# interceptor.net
KiCad netlist of a schematic drawn in EAGLE
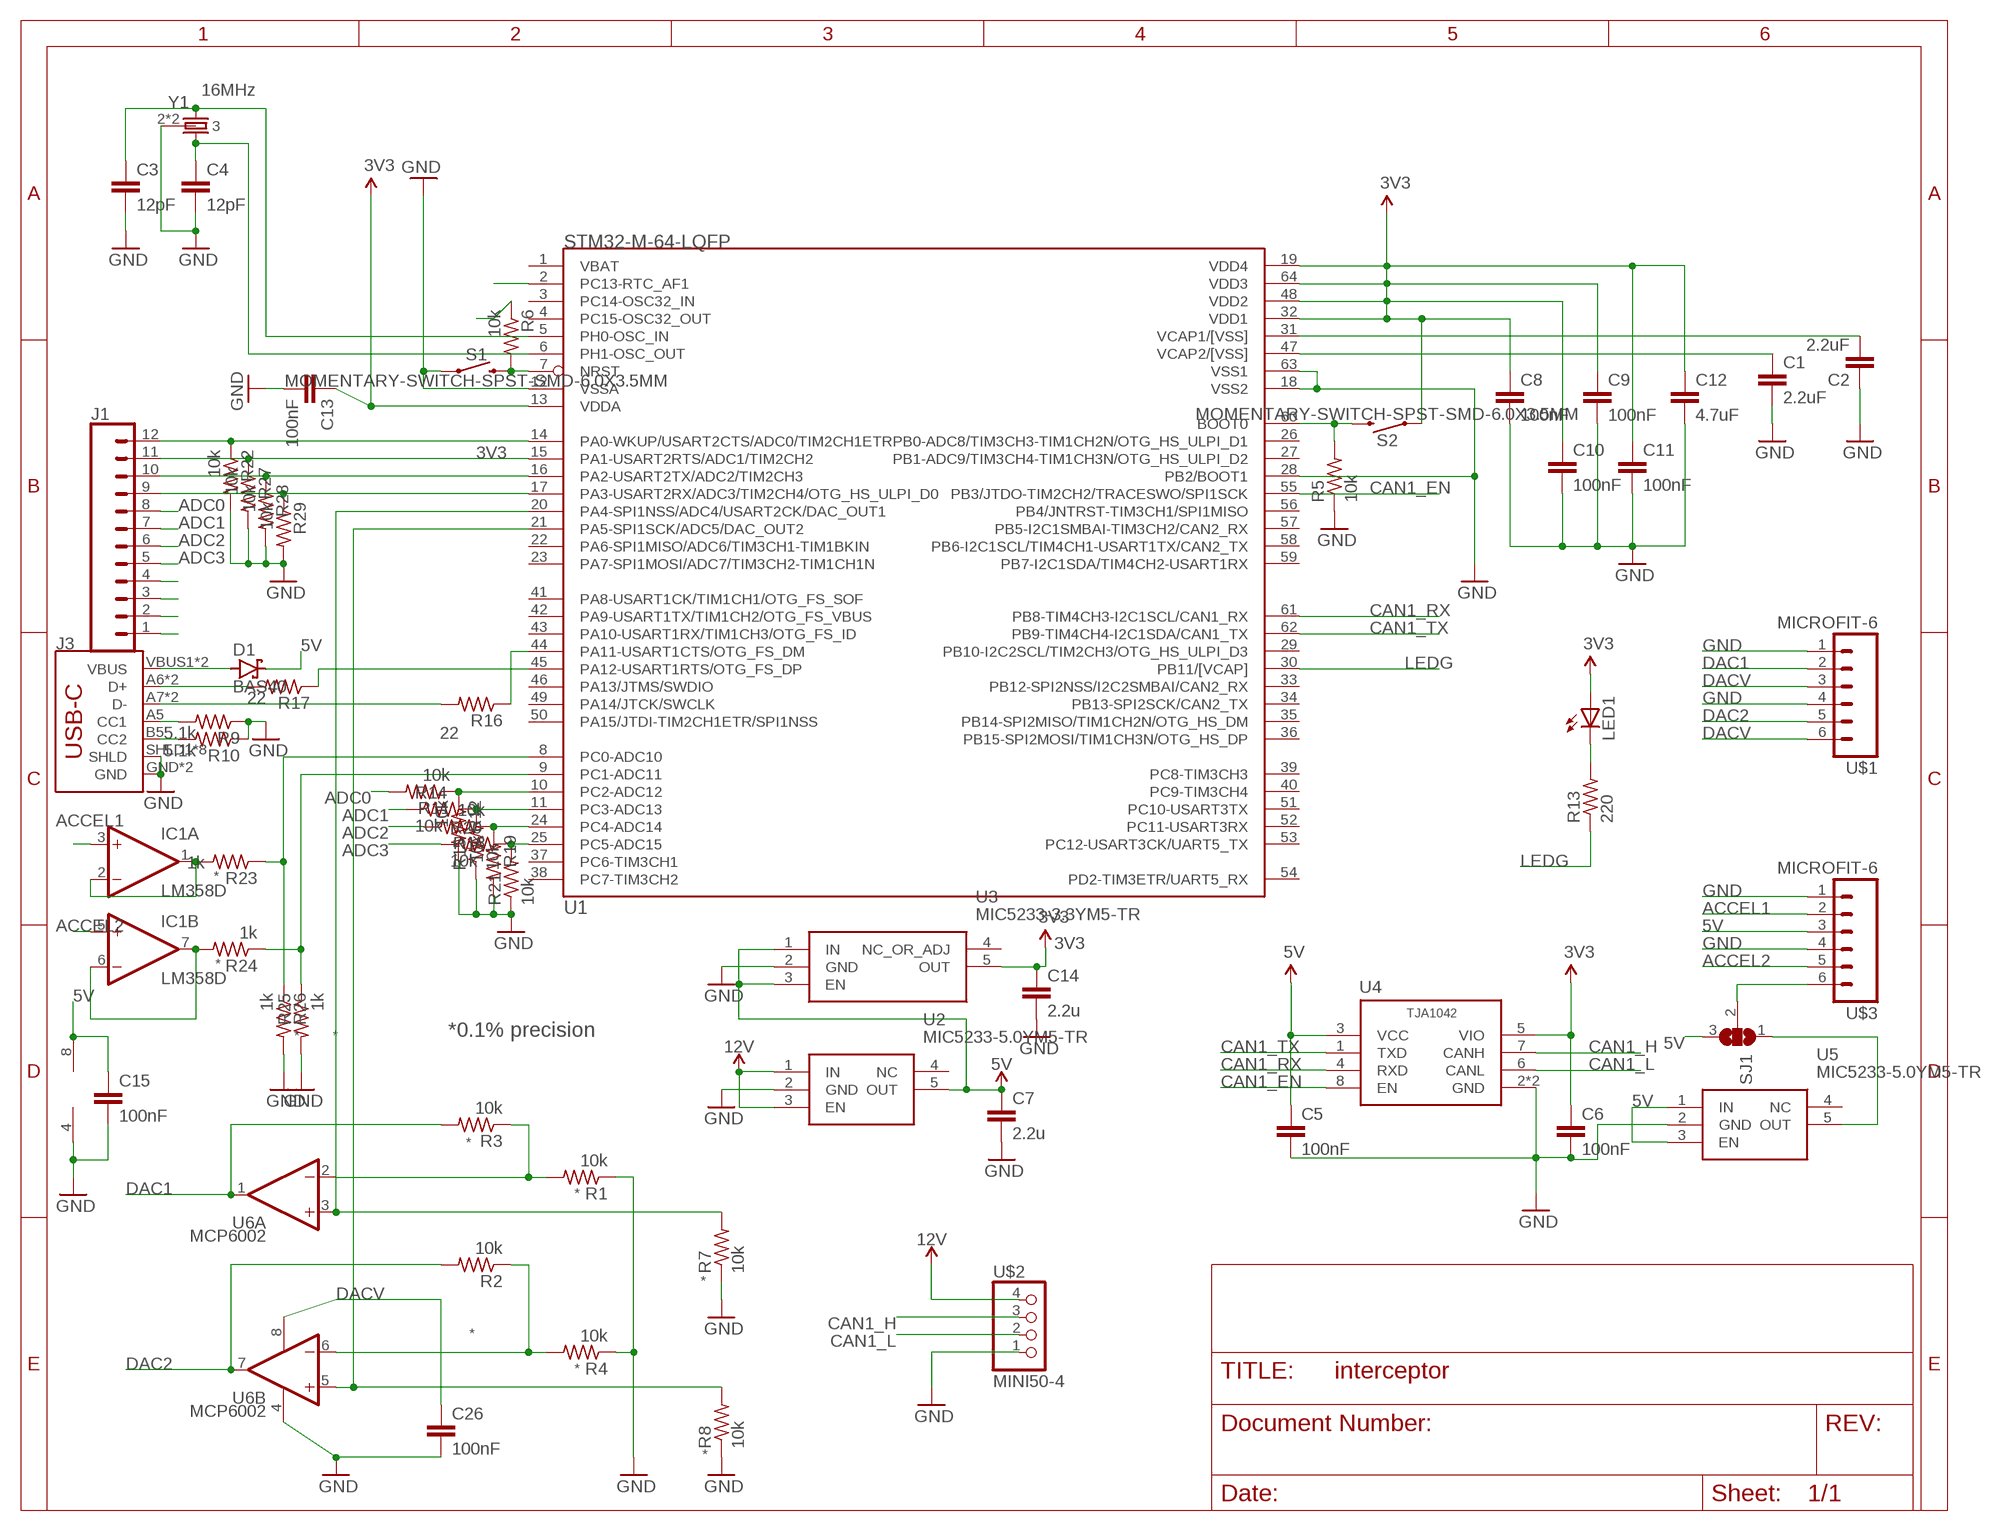
[diagram p0: schematic, sheet 1]

(export (version "E")
  (design (tool "Eeschema 10.0.6"))
  (components
    (comp (ref "C1")
      (value "2.2uF")
      (footprint "eagle-import:0603-C")
      (libsource (lib "eagle-import") (part "C0603"))
    )
    (comp (ref "C2")
      (value "2.2uF")
      (footprint "eagle-import:0603-C")
      (libsource (lib "eagle-import") (part "C0603"))
    )
    (comp (ref "C3")
      (value "12pF")
      (footprint "eagle-import:0603-C")
      (libsource (lib "eagle-import") (part "C0603"))
    )
    (comp (ref "C4")
      (value "12pF")
      (footprint "eagle-import:0603-C")
      (libsource (lib "eagle-import") (part "C0603"))
    )
    (comp (ref "C5")
      (value "100nF")
      (footprint "eagle-import:0603-C")
      (libsource (lib "eagle-import") (part "C0603"))
    )
    (comp (ref "C6")
      (value "100nF")
      (footprint "eagle-import:0603-C")
      (libsource (lib "eagle-import") (part "C0603"))
    )
    (comp (ref "C7")
      (value "2.2u")
      (footprint "eagle-import:C0603")
      (libsource (lib "eagle-import") (part "C-EUC0603"))
    )
    (comp (ref "C8")
      (value "100nF")
      (footprint "eagle-import:0603-C")
      (libsource (lib "eagle-import") (part "C0603"))
    )
    (comp (ref "C9")
      (value "100nF")
      (footprint "eagle-import:0603-C")
      (libsource (lib "eagle-import") (part "C0603"))
    )
    (comp (ref "C10")
      (value "100nF")
      (footprint "eagle-import:0603-C")
      (libsource (lib "eagle-import") (part "C0603"))
    )
    (comp (ref "C11")
      (value "100nF")
      (footprint "eagle-import:0603-C")
      (libsource (lib "eagle-import") (part "C0603"))
    )
    (comp (ref "C12")
      (value "4.7uF")
      (footprint "eagle-import:0603-C")
      (libsource (lib "eagle-import") (part "C0603"))
    )
    (comp (ref "C13")
      (value "100nF")
      (footprint "eagle-import:0603-C")
      (libsource (lib "eagle-import") (part "C0603"))
    )
    (comp (ref "C14")
      (value "2.2u")
      (footprint "eagle-import:C0603")
      (libsource (lib "eagle-import") (part "C-EUC0603"))
    )
    (comp (ref "C15")
      (value "100nF")
      (footprint "eagle-import:0603-C")
      (libsource (lib "eagle-import") (part "C0603"))
    )
    (comp (ref "C26")
      (value "100nF")
      (footprint "eagle-import:0603-C")
      (libsource (lib "eagle-import") (part "C0603"))
    )
    (comp (ref "D1")
      (value "BAS40")
      (footprint "eagle-import:SOT23")
      (libsource (lib "eagle-import") (part "BAS40"))
    )
    (comp (ref "IC1")
      (value "LM358D")
      (footprint "eagle-import:SO08")
      (libsource (lib "eagle-import") (part "LM358D"))
    )
    (comp (ref "J1")
      (value "CONN_12")
      (footprint "eagle-import:1X12")
      (libsource (lib "eagle-import") (part "CONN_12"))
    )
    (comp (ref "J3")
      (value "USB-C-BREAKOUT_SPARKFUN-CONNECTORS_USB_C16PIN")
      (footprint "eagle-import:USB-C-BREAKOUT_SPARKFUN-CONNECTORS_USB-C-16P")
      (libsource (lib "eagle-import") (part "USB-C-BREAKOUT_SPARKFUN-CONNECTORS_USB_C16PIN"))
    )
    (comp (ref "LED1")
      (value "LEDCHIPLED_0805")
      (footprint "eagle-import:CHIPLED_0805")
      (libsource (lib "eagle-import") (part "LEDCHIPLED_0805"))
    )
    (comp (ref "R1")
      (value "10k")
      (footprint "eagle-import:0402-R")
      (libsource (lib "eagle-import") (part "R0402"))
    )
    (comp (ref "R2")
      (value "10k")
      (footprint "eagle-import:0402-R")
      (libsource (lib "eagle-import") (part "R0402"))
    )
    (comp (ref "R3")
      (value "10k")
      (footprint "eagle-import:0402-R")
      (libsource (lib "eagle-import") (part "R0402"))
    )
    (comp (ref "R4")
      (value "10k")
      (footprint "eagle-import:0402-R")
      (libsource (lib "eagle-import") (part "R0402"))
    )
    (comp (ref "R5")
      (value "10k")
      (footprint "eagle-import:0402-R")
      (libsource (lib "eagle-import") (part "R0402"))
    )
    (comp (ref "R6")
      (value "10k")
      (footprint "eagle-import:0402-R")
      (libsource (lib "eagle-import") (part "R0402"))
    )
    (comp (ref "R7")
      (value "10k")
      (footprint "eagle-import:0402-R")
      (libsource (lib "eagle-import") (part "R0402"))
    )
    (comp (ref "R8")
      (value "10k")
      (footprint "eagle-import:0402-R")
      (libsource (lib "eagle-import") (part "R0402"))
    )
    (comp (ref "R9")
      (value "5.1k")
      (footprint "eagle-import:0402-R")
      (libsource (lib "eagle-import") (part "R0402"))
    )
    (comp (ref "R10")
      (value "5.1k")
      (footprint "eagle-import:0402-R")
      (libsource (lib "eagle-import") (part "R0402"))
    )
    (comp (ref "R11")
      (value "10k")
      (footprint "eagle-import:0402-R")
      (libsource (lib "eagle-import") (part "R0402"))
    )
    (comp (ref "R12")
      (value "10k")
      (footprint "eagle-import:0402-R")
      (libsource (lib "eagle-import") (part "R0402"))
    )
    (comp (ref "R13")
      (value "220")
      (footprint "eagle-import:0402-R")
      (libsource (lib "eagle-import") (part "R0402"))
    )
    (comp (ref "R14")
      (value "10k")
      (footprint "eagle-import:0402-R")
      (libsource (lib "eagle-import") (part "R0402"))
    )
    (comp (ref "R15")
      (value "10k")
      (footprint "eagle-import:0402-R")
      (libsource (lib "eagle-import") (part "R0402"))
    )
    (comp (ref "R16")
      (value "22")
      (footprint "eagle-import:0402-R")
      (libsource (lib "eagle-import") (part "R0402"))
    )
    (comp (ref "R17")
      (value "22")
      (footprint "eagle-import:0402-R")
      (libsource (lib "eagle-import") (part "R0402"))
    )
    (comp (ref "R18")
      (value "10k")
      (footprint "eagle-import:0402-R")
      (libsource (lib "eagle-import") (part "R0402"))
    )
    (comp (ref "R19")
      (value "10k")
      (footprint "eagle-import:0402-R")
      (libsource (lib "eagle-import") (part "R0402"))
    )
    (comp (ref "R20")
      (value "10k")
      (footprint "eagle-import:0402-R")
      (libsource (lib "eagle-import") (part "R0402"))
    )
    (comp (ref "R21")
      (value "10k")
      (footprint "eagle-import:0402-R")
      (libsource (lib "eagle-import") (part "R0402"))
    )
    (comp (ref "R22")
      (value "10k")
      (footprint "eagle-import:0402-R")
      (libsource (lib "eagle-import") (part "R0402"))
    )
    (comp (ref "R23")
      (value "1k")
      (footprint "eagle-import:0402-R")
      (libsource (lib "eagle-import") (part "R0402"))
    )
    (comp (ref "R24")
      (value "1k")
      (footprint "eagle-import:0402-R")
      (libsource (lib "eagle-import") (part "R0402"))
    )
    (comp (ref "R25")
      (value "1k")
      (footprint "eagle-import:0402-R")
      (libsource (lib "eagle-import") (part "R0402"))
    )
    (comp (ref "R26")
      (value "1k")
      (footprint "eagle-import:0402-R")
      (libsource (lib "eagle-import") (part "R0402"))
    )
    (comp (ref "R27")
      (value "10k")
      (footprint "eagle-import:0402-R")
      (libsource (lib "eagle-import") (part "R0402"))
    )
    (comp (ref "R28")
      (value "10k")
      (footprint "eagle-import:0402-R")
      (libsource (lib "eagle-import") (part "R0402"))
    )
    (comp (ref "R29")
      (value "10k")
      (footprint "eagle-import:0402-R")
      (libsource (lib "eagle-import") (part "R0402"))
    )
    (comp (ref "S1")
      (value "MOMENTARY-SWITCH-SPST-SMD-6.0X3.5MM")
      (footprint "eagle-import:TACTILE_SWITCH_SMD_6.0X3.5MM")
      (libsource (lib "eagle-import") (part "MOMENTARY-SWITCH-SPST-SMD-6.0X3.5MM"))
    )
    (comp (ref "S2")
      (value "MOMENTARY-SWITCH-SPST-SMD-6.0X3.5MM")
      (footprint "eagle-import:TACTILE_SWITCH_SMD_6.0X3.5MM")
      (libsource (lib "eagle-import") (part "MOMENTARY-SWITCH-SPST-SMD-6.0X3.5MM"))
    )
    (comp (ref "SJ1")
      (value "SJ2W")
      (footprint "eagle-import:SJ_2")
      (libsource (lib "eagle-import") (part "SJ2W"))
    )
    (comp (ref "U$1")
      (value "MICROFIT-6")
      (footprint "eagle-import:MICROFIT-6")
      (libsource (lib "eagle-import") (part "MICROFIT-6"))
    )
    (comp (ref "U$2")
      (value "MINI50-4")
      (footprint "eagle-import:MINI50")
      (libsource (lib "eagle-import") (part "MINI50-4"))
    )
    (comp (ref "U$3")
      (value "MICROFIT-6")
      (footprint "eagle-import:MICROFIT-6")
      (libsource (lib "eagle-import") (part "MICROFIT-6"))
    )
    (comp (ref "U1")
      (value "STM32-M-64-LQFP")
      (footprint "eagle-import:LQFP64")
      (libsource (lib "eagle-import") (part "STM32-M-64-LQFP"))
    )
    (comp (ref "U2")
      (value "MIC5233-5.0YM5-TR")
      (footprint "eagle-import:SOT95P280X145-5N")
      (fields (field (name "MOUSER_PART_NUMBER") "998-MIC5233-5.0YM5TR"))
      (libsource (lib "eagle-import") (part "MIC5233-5.0YM5-TR"))
    )
    (comp (ref "U3")
      (value "MIC5233-3.3YM5-TR")
      (footprint "eagle-import:SOT95P280X145-5N")
      (fields (field (name "MOUSER_PART_NUMBER") "998-MIC5233-3.3YM5TR"))
      (libsource (lib "eagle-import") (part "MIC5233-3.3YM5-TR"))
    )
    (comp (ref "U4")
      (value "TJA1042HVSON")
      (footprint "eagle-import:HVSON8")
      (libsource (lib "eagle-import") (part "TJA1042HVSON"))
    )
    (comp (ref "U5")
      (value "MIC5233-5.0YM5-TR")
      (footprint "eagle-import:SOT95P280X145-5N")
      (fields (field (name "MOUSER_PART_NUMBER") "998-MIC5233-5.0YM5TR"))
      (libsource (lib "eagle-import") (part "MIC5233-5.0YM5-TR"))
    )
    (comp (ref "U6")
      (value "MCP6002")
      (footprint "eagle-import:SO08")
      (libsource (lib "eagle-import") (part "LM358D"))
    )
    (comp (ref "Y1")
      (value "16MHz")
      (footprint "eagle-import:XTAL-3.2X2.5")
      (libsource (lib "eagle-import") (part "CRYSTAL-3.2X2.54-PIN"))
    )
  )
  (nets
    (net (code "1") (name "/ACCEL1") (class "Default")
      (node (ref "IC1") (pin "3") (pinfunction "+IN_3") (pintype "input"))
      (node (ref "U$3") (pin "2") (pinfunction "2_2") (pintype "passive"))
    )
    (net (code "2") (name "/ACCEL2") (class "Default")
      (node (ref "IC1") (pin "5") (pinfunction "+IN_5") (pintype "input"))
      (node (ref "U$3") (pin "5") (pinfunction "5_5") (pintype "passive"))
    )
    (net (code "3") (name "/ADC0") (class "Default")
      (node (ref "J1") (pin "8") (pinfunction "8_8") (pintype "passive"))
      (node (ref "R11") (pin "2") (pinfunction "2_2") (pintype "passive"))
    )
    (net (code "4") (name "/ADC1") (class "Default")
      (node (ref "J1") (pin "7") (pinfunction "7_7") (pintype "passive"))
      (node (ref "R14") (pin "1") (pinfunction "1_1") (pintype "passive"))
    )
    (net (code "5") (name "/ADC2") (class "Default")
      (node (ref "J1") (pin "6") (pinfunction "6_6") (pintype "passive"))
      (node (ref "R18") (pin "2") (pinfunction "2_2") (pintype "passive"))
    )
    (net (code "6") (name "/ADC3") (class "Default")
      (node (ref "J1") (pin "5") (pinfunction "5_5") (pintype "passive"))
      (node (ref "R20") (pin "1") (pinfunction "1_1") (pintype "passive"))
    )
    (net (code "7") (name "/CAN1_EN") (class "Default")
      (node (ref "U1") (pin "55") (pinfunction "PB3/JTDO-TIM2CH2/TRACESWO/SPI1SCK_55") (pintype "bidirectional"))
      (node (ref "U4") (pin "8") (pinfunction "EN_8") (pintype "bidirectional"))
    )
    (net (code "8") (name "/CAN1_H") (class "Default")
      (node (ref "U$2") (pin "3") (pinfunction "2_3") (pintype "passive"))
      (node (ref "U4") (pin "7") (pinfunction "CANH_7") (pintype "bidirectional"))
    )
    (net (code "9") (name "/CAN1_L") (class "Default")
      (node (ref "U$2") (pin "2") (pinfunction "3_2") (pintype "passive"))
      (node (ref "U4") (pin "6") (pinfunction "CANL_6") (pintype "bidirectional"))
    )
    (net (code "10") (name "/CAN1_RX") (class "Default")
      (node (ref "U1") (pin "61") (pinfunction "PB8-TIM4CH3-I2C1SCL/CAN1_RX_61") (pintype "bidirectional"))
      (node (ref "U4") (pin "4") (pinfunction "RXD_4") (pintype "bidirectional"))
    )
    (net (code "11") (name "/CAN1_TX") (class "Default")
      (node (ref "U1") (pin "62") (pinfunction "PB9-TIM4CH4-I2C1SDA/CAN1_TX_62") (pintype "bidirectional"))
      (node (ref "U4") (pin "1") (pinfunction "TXD_1") (pintype "bidirectional"))
    )
    (net (code "12") (name "/DAC1") (class "Default")
      (node (ref "R3") (pin "2") (pinfunction "2_2") (pintype "passive"))
      (node (ref "U$1") (pin "2") (pinfunction "2_2") (pintype "passive"))
      (node (ref "U6") (pin "1") (pinfunction "OUT_1") (pintype "output"))
    )
    (net (code "13") (name "/DAC2") (class "Default")
      (node (ref "R2") (pin "2") (pinfunction "2_2") (pintype "passive"))
      (node (ref "U$1") (pin "5") (pinfunction "5_5") (pintype "passive"))
      (node (ref "U6") (pin "7") (pinfunction "OUT_7") (pintype "output"))
    )
    (net (code "14") (name "/DACV") (class "Default")
      (node (ref "C26") (pin "1") (pinfunction "1_1") (pintype "passive"))
      (node (ref "U$1") (pin "3") (pinfunction "3_3") (pintype "passive"))
      (node (ref "U$1") (pin "6") (pinfunction "6_6") (pintype "passive"))
      (node (ref "U6") (pin "8") (pinfunction "V+_8") (pintype "power_in"))
    )
    (net (code "15") (name "/LEDG") (class "Default")
      (node (ref "R13") (pin "1") (pinfunction "1_1") (pintype "passive"))
      (node (ref "U1") (pin "30") (pinfunction "PB11/[VCAP]_30") (pintype "bidirectional"))
    )
    (net (code "16") (name "/VBAT") (class "Default")
      (node (ref "U1") (pin "1") (pinfunction "VBAT_1") (pintype "power_in"))
    )
    (net (code "17") (name "3V3") (class "Default")
      (node (ref "C10") (pin "1") (pinfunction "1_1") (pintype "passive"))
      (node (ref "C11") (pin "1") (pinfunction "1_1") (pintype "passive"))
      (node (ref "C12") (pin "1") (pinfunction "1_1") (pintype "passive"))
      (node (ref "C13") (pin "1") (pinfunction "1_1") (pintype "passive"))
      (node (ref "C14") (pin "1") (pinfunction "1_1") (pintype "passive"))
      (node (ref "C6") (pin "1") (pinfunction "1_1") (pintype "passive"))
      (node (ref "C8") (pin "1") (pinfunction "1_1") (pintype "passive"))
      (node (ref "C9") (pin "1") (pinfunction "1_1") (pintype "passive"))
      (node (ref "LED1") (pin "A") (pinfunction "A_A") (pintype "passive"))
      (node (ref "R6") (pin "1") (pinfunction "1_1") (pintype "passive"))
      (node (ref "S2") (pin "1") (pinfunction "1_1") (pintype "passive"))
      (node (ref "U1") (pin "13") (pinfunction "VDDA_13") (pintype "power_in"))
      (node (ref "U1") (pin "19") (pinfunction "VDD4_19") (pintype "bidirectional"))
      (node (ref "U1") (pin "32") (pinfunction "VDD1_32") (pintype "power_in"))
      (node (ref "U1") (pin "48") (pinfunction "VDD2_48") (pintype "power_in"))
      (node (ref "U1") (pin "64") (pinfunction "VDD3_64") (pintype "power_in"))
      (node (ref "U3") (pin "5") (pinfunction "OUT_5") (pintype "bidirectional"))
      (node (ref "U4") (pin "5") (pinfunction "VIO_5") (pintype "bidirectional"))
    )
    (net (code "18") (name "5V") (class "Default")
      (node (ref "C15") (pin "1") (pinfunction "1_1") (pintype "passive"))
      (node (ref "C5") (pin "1") (pinfunction "1_1") (pintype "passive"))
      (node (ref "C7") (pin "1") (pinfunction "1_1") (pintype "passive"))
      (node (ref "D1") (pin "3") (pinfunction "C_3") (pintype "passive"))
      (node (ref "IC1") (pin "8") (pinfunction "V+_8") (pintype "power_in"))
      (node (ref "SJ1") (pin "3") (pinfunction "3_3") (pintype "passive"))
      (node (ref "U$3") (pin "3") (pinfunction "3_3") (pintype "passive"))
      (node (ref "U2") (pin "5") (pinfunction "OUT_5") (pintype "bidirectional"))
      (node (ref "U3") (pin "1") (pinfunction "IN_1") (pintype "bidirectional"))
      (node (ref "U3") (pin "3") (pinfunction "EN_3") (pintype "bidirectional"))
      (node (ref "U4") (pin "3") (pinfunction "VCC_3") (pintype "bidirectional"))
      (node (ref "U5") (pin "1") (pinfunction "IN_1") (pintype "bidirectional"))
      (node (ref "U5") (pin "3") (pinfunction "EN_3") (pintype "bidirectional"))
    )
    (net (code "19") (name "12V") (class "Default")
      (node (ref "U$2") (pin "4") (pinfunction "1_4") (pintype "passive"))
      (node (ref "U2") (pin "1") (pinfunction "IN_1") (pintype "bidirectional"))
      (node (ref "U2") (pin "3") (pinfunction "EN_3") (pintype "bidirectional"))
    )
    (net (code "20") (name "GND") (class "Default")
      (node (ref "C1") (pin "2") (pinfunction "2_2") (pintype "passive"))
      (node (ref "C10") (pin "2") (pinfunction "2_2") (pintype "passive"))
      (node (ref "C11") (pin "2") (pinfunction "2_2") (pintype "passive"))
      (node (ref "C12") (pin "2") (pinfunction "2_2") (pintype "passive"))
      (node (ref "C13") (pin "2") (pinfunction "2_2") (pintype "passive"))
      (node (ref "C14") (pin "2") (pinfunction "2_2") (pintype "passive"))
      (node (ref "C15") (pin "2") (pinfunction "2_2") (pintype "passive"))
      (node (ref "C2") (pin "1") (pinfunction "1_1") (pintype "passive"))
      (node (ref "C26") (pin "2") (pinfunction "2_2") (pintype "passive"))
      (node (ref "C3") (pin "2") (pinfunction "2_2") (pintype "passive"))
      (node (ref "C4") (pin "2") (pinfunction "2_2") (pintype "passive"))
      (node (ref "C5") (pin "2") (pinfunction "2_2") (pintype "passive"))
      (node (ref "C6") (pin "2") (pinfunction "2_2") (pintype "passive"))
      (node (ref "C7") (pin "2") (pinfunction "2_2") (pintype "passive"))
      (node (ref "C8") (pin "2") (pinfunction "2_2") (pintype "passive"))
      (node (ref "C9") (pin "2") (pinfunction "2_2") (pintype "passive"))
      (node (ref "IC1") (pin "4") (pinfunction "V-_4") (pintype "power_in"))
      (node (ref "J3") (pin "GND") (pinfunction "GND_GND") (pintype "bidirectional"))
      (node (ref "J3") (pin "GND2") (pinfunction "GND_GND2") (pintype "bidirectional"))
      (node (ref "J3") (pin "SHLD1") (pinfunction "SHLD_SHLD1") (pintype "bidirectional"))
      (node (ref "J3") (pin "SHLD2") (pinfunction "SHLD_SHLD2") (pintype "bidirectional"))
      (node (ref "J3") (pin "SHLD3") (pinfunction "SHLD_SHLD3") (pintype "bidirectional"))
      (node (ref "J3") (pin "SHLD4") (pinfunction "SHLD_SHLD4") (pintype "bidirectional"))
      (node (ref "J3") (pin "SHLD5") (pinfunction "SHLD_SHLD5") (pintype "bidirectional"))
      (node (ref "J3") (pin "SHLD6") (pinfunction "SHLD_SHLD6") (pintype "bidirectional"))
      (node (ref "J3") (pin "SHLD7") (pinfunction "SHLD_SHLD7") (pintype "bidirectional"))
      (node (ref "J3") (pin "SHLD8") (pinfunction "SHLD_SHLD8") (pintype "bidirectional"))
      (node (ref "R1") (pin "1") (pinfunction "1_1") (pintype "passive"))
      (node (ref "R10") (pin "1") (pinfunction "1_1") (pintype "passive"))
      (node (ref "R12") (pin "2") (pinfunction "2_2") (pintype "passive"))
      (node (ref "R15") (pin "1") (pinfunction "1_1") (pintype "passive"))
      (node (ref "R19") (pin "2") (pinfunction "2_2") (pintype "passive"))
      (node (ref "R21") (pin "1") (pinfunction "1_1") (pintype "passive"))
      (node (ref "R22") (pin "2") (pinfunction "2_2") (pintype "passive"))
      (node (ref "R25") (pin "2") (pinfunction "2_2") (pintype "passive"))
      (node (ref "R26") (pin "2") (pinfunction "2_2") (pintype "passive"))
      (node (ref "R27") (pin "2") (pinfunction "2_2") (pintype "passive"))
      (node (ref "R28") (pin "2") (pinfunction "2_2") (pintype "passive"))
      (node (ref "R29") (pin "2") (pinfunction "2_2") (pintype "passive"))
      (node (ref "R4") (pin "1") (pinfunction "1_1") (pintype "passive"))
      (node (ref "R5") (pin "1") (pinfunction "1_1") (pintype "passive"))
      (node (ref "R7") (pin "1") (pinfunction "1_1") (pintype "passive"))
      (node (ref "R8") (pin "1") (pinfunction "1_1") (pintype "passive"))
      (node (ref "R9") (pin "1") (pinfunction "1_1") (pintype "passive"))
      (node (ref "S1") (pin "1") (pinfunction "1_1") (pintype "passive"))
      (node (ref "U$1") (pin "1") (pinfunction "1_1") (pintype "passive"))
      (node (ref "U$1") (pin "4") (pinfunction "4_4") (pintype "passive"))
      (node (ref "U$2") (pin "1") (pinfunction "4_1") (pintype "passive"))
      (node (ref "U$3") (pin "1") (pinfunction "1_1") (pintype "passive"))
      (node (ref "U$3") (pin "4") (pinfunction "4_4") (pintype "passive"))
      (node (ref "U1") (pin "12") (pinfunction "VSSA_12") (pintype "power_in"))
      (node (ref "U1") (pin "18") (pinfunction "VSS2_18") (pintype "bidirectional"))
      (node (ref "U1") (pin "28") (pinfunction "PB2/BOOT1_28") (pintype "bidirectional"))
      (node (ref "U1") (pin "63") (pinfunction "VSS1_63") (pintype "power_in"))
      (node (ref "U2") (pin "2") (pinfunction "GND_2") (pintype "bidirectional"))
      (node (ref "U3") (pin "2") (pinfunction "GND_2") (pintype "bidirectional"))
      (node (ref "U4") (pin "2") (pinfunction "GND_2") (pintype "bidirectional"))
      (node (ref "U4") (pin "PAD") (pinfunction "GND_PAD") (pintype "bidirectional"))
      (node (ref "U5") (pin "2") (pinfunction "GND_2") (pintype "bidirectional"))
      (node (ref "U6") (pin "4") (pinfunction "V-_4") (pintype "power_in"))
      (node (ref "Y1") (pin "2") (pinfunction "3_2") (pintype "bidirectional"))
      (node (ref "Y1") (pin "4") (pinfunction "3_4") (pintype "bidirectional"))
    )
    (net (code "21") (name "Net-(D1-A)") (class "Default")
      (node (ref "D1") (pin "1") (pinfunction "A_1") (pintype "passive"))
      (node (ref "J3") (pin "VBUS1") (pinfunction "VBUS_VBUS1") (pintype "bidirectional"))
      (node (ref "J3") (pin "VBUS2") (pinfunction "VBUS_VBUS2") (pintype "bidirectional"))
    )
    (net (code "22") (name "Net-(IC1A--IN)") (class "Default")
      (node (ref "IC1") (pin "1") (pinfunction "OUT_1") (pintype "output"))
      (node (ref "IC1") (pin "2") (pinfunction "-IN_2") (pintype "input"))
      (node (ref "R23") (pin "2") (pinfunction "2_2") (pintype "passive"))
    )
    (net (code "23") (name "Net-(IC1B--IN)") (class "Default")
      (node (ref "IC1") (pin "6") (pinfunction "-IN_6") (pintype "input"))
      (node (ref "IC1") (pin "7") (pinfunction "OUT_7") (pintype "output"))
      (node (ref "R24") (pin "2") (pinfunction "2_2") (pintype "passive"))
    )
    (net (code "24") (name "Net-(J3-CC1)") (class "Default")
      (node (ref "J3") (pin "A5") (pinfunction "CC1_A5") (pintype "bidirectional"))
      (node (ref "R9") (pin "2") (pinfunction "2_2") (pintype "passive"))
    )
    (net (code "25") (name "Net-(J3-CC2)") (class "Default")
      (node (ref "J3") (pin "B5") (pinfunction "CC2_B5") (pintype "bidirectional"))
      (node (ref "R10") (pin "2") (pinfunction "2_2") (pintype "passive"))
    )
    (net (code "26") (name "Net-(J3-D+-PadA6)") (class "Default")
      (node (ref "J3") (pin "A6") (pinfunction "D+_A6") (pintype "bidirectional"))
      (node (ref "J3") (pin "B6") (pinfunction "D+_B6") (pintype "bidirectional"))
      (node (ref "R17") (pin "2") (pinfunction "2_2") (pintype "passive"))
    )
    (net (code "27") (name "Net-(J3-D--PadA7)") (class "Default")
      (node (ref "J3") (pin "A7") (pinfunction "D-_A7") (pintype "bidirectional"))
      (node (ref "J3") (pin "B7") (pinfunction "D-_B7") (pintype "bidirectional"))
      (node (ref "R16") (pin "2") (pinfunction "2_2") (pintype "passive"))
    )
    (net (code "28") (name "Net-(LED1-PadC)") (class "Default")
      (node (ref "LED1") (pin "C") (pinfunction "C_C") (pintype "passive"))
      (node (ref "R13") (pin "2") (pinfunction "2_2") (pintype "passive"))
    )
    (net (code "29") (name "Net-(SJ1-Pad2)") (class "Default")
      (node (ref "SJ1") (pin "2") (pinfunction "2_2") (pintype "passive"))
      (node (ref "U$3") (pin "6") (pinfunction "6_6") (pintype "passive"))
    )
    (net (code "30") (name "Net-(U1-BOOT0)") (class "Default")
      (node (ref "R5") (pin "2") (pinfunction "2_2") (pintype "passive"))
      (node (ref "S2") (pin "2") (pinfunction "2_2") (pintype "passive"))
      (node (ref "U1") (pin "60") (pinfunction "BOOT0_60") (pintype "input"))
    )
    (net (code "31") (name "Net-(U1-NRST)") (class "Default")
      (node (ref "R6") (pin "2") (pinfunction "2_2") (pintype "passive"))
      (node (ref "S1") (pin "2") (pinfunction "2_2") (pintype "passive"))
      (node (ref "U1") (pin "7") (pinfunction "NRST_7") (pintype "bidirectional"))
    )
    (net (code "32") (name "Net-(U1-PA0-WKUP{slash}USART2CTS{slash}ADC0{slash}TIM2CH1ETR)") (class "Default")
      (node (ref "J1") (pin "12") (pinfunction "12_12") (pintype "passive"))
      (node (ref "R22") (pin "1") (pinfunction "1_1") (pintype "passive"))
      (node (ref "U1") (pin "14") (pinfunction "PA0-WKUP/USART2CTS/ADC0/TIM2CH1ETR_14") (pintype "bidirectional"))
    )
    (net (code "33") (name "Net-(U1-PA1-USART2RTS{slash}ADC1{slash}TIM2CH2)") (class "Default")
      (node (ref "J1") (pin "11") (pinfunction "11_11") (pintype "passive"))
      (node (ref "R27") (pin "1") (pinfunction "1_1") (pintype "passive"))
      (node (ref "U1") (pin "15") (pinfunction "PA1-USART2RTS/ADC1/TIM2CH2_15") (pintype "bidirectional"))
    )
    (net (code "34") (name "Net-(U1-PA2-USART2TX{slash}ADC2{slash}TIM2CH3)") (class "Default")
      (node (ref "J1") (pin "10") (pinfunction "10_10") (pintype "passive"))
      (node (ref "R28") (pin "1") (pinfunction "1_1") (pintype "passive"))
      (node (ref "U1") (pin "16") (pinfunction "PA2-USART2TX/ADC2/TIM2CH3_16") (pintype "bidirectional"))
    )
    (net (code "35") (name "Net-(U1-PA3-USART2RX{slash}ADC3{slash}TIM2CH4{slash}OTG_HS_ULPI_D0)") (class "Default")
      (node (ref "J1") (pin "9") (pinfunction "9_9") (pintype "passive"))
      (node (ref "R29") (pin "1") (pinfunction "1_1") (pintype "passive"))
      (node (ref "U1") (pin "17") (pinfunction "PA3-USART2RX/ADC3/TIM2CH4/OTG_HS_ULPI_D0_17") (pintype "bidirectional"))
    )
    (net (code "36") (name "Net-(U1-PA4-SPI1NSS{slash}ADC4{slash}USART2CK{slash}DAC_OUT1)") (class "Default")
      (node (ref "R7") (pin "2") (pinfunction "2_2") (pintype "passive"))
      (node (ref "U1") (pin "20") (pinfunction "PA4-SPI1NSS/ADC4/USART2CK/DAC_OUT1_20") (pintype "bidirectional"))
      (node (ref "U6") (pin "3") (pinfunction "+IN_3") (pintype "input"))
    )
    (net (code "37") (name "Net-(U1-PA5-SPI1SCK{slash}ADC5{slash}DAC_OUT2)") (class "Default")
      (node (ref "R8") (pin "2") (pinfunction "2_2") (pintype "passive"))
      (node (ref "U1") (pin "21") (pinfunction "PA5-SPI1SCK/ADC5/DAC_OUT2_21") (pintype "bidirectional"))
      (node (ref "U6") (pin "5") (pinfunction "+IN_5") (pintype "input"))
    )
    (net (code "38") (name "Net-(U1-PA11-USART1CTS{slash}OTG_FS_DM)") (class "Default")
      (node (ref "R16") (pin "1") (pinfunction "1_1") (pintype "passive"))
      (node (ref "U1") (pin "44") (pinfunction "PA11-USART1CTS/OTG_FS_DM_44") (pintype "bidirectional"))
    )
    (net (code "39") (name "Net-(U1-PA12-USART1RTS{slash}OTG_FS_DP)") (class "Default")
      (node (ref "R17") (pin "1") (pinfunction "1_1") (pintype "passive"))
      (node (ref "U1") (pin "45") (pinfunction "PA12-USART1RTS/OTG_FS_DP_45") (pintype "bidirectional"))
    )
    (net (code "40") (name "Net-(U1-PC0-ADC10)") (class "Default")
      (node (ref "R23") (pin "1") (pinfunction "1_1") (pintype "passive"))
      (node (ref "R26") (pin "1") (pinfunction "1_1") (pintype "passive"))
      (node (ref "U1") (pin "8") (pinfunction "PC0-ADC10_8") (pintype "bidirectional"))
    )
    (net (code "41") (name "Net-(U1-PC1-ADC11)") (class "Default")
      (node (ref "R24") (pin "1") (pinfunction "1_1") (pintype "passive"))
      (node (ref "R25") (pin "1") (pinfunction "1_1") (pintype "passive"))
      (node (ref "U1") (pin "9") (pinfunction "PC1-ADC11_9") (pintype "bidirectional"))
    )
    (net (code "42") (name "Net-(U1-PC2-ADC12)") (class "Default")
      (node (ref "R11") (pin "1") (pinfunction "1_1") (pintype "passive"))
      (node (ref "R12") (pin "1") (pinfunction "1_1") (pintype "passive"))
      (node (ref "U1") (pin "10") (pinfunction "PC2-ADC12_10") (pintype "bidirectional"))
    )
    (net (code "43") (name "Net-(U1-PC3-ADC13)") (class "Default")
      (node (ref "R14") (pin "2") (pinfunction "2_2") (pintype "passive"))
      (node (ref "R15") (pin "2") (pinfunction "2_2") (pintype "passive"))
      (node (ref "U1") (pin "11") (pinfunction "PC3-ADC13_11") (pintype "bidirectional"))
    )
    (net (code "44") (name "Net-(U1-PC4-ADC14)") (class "Default")
      (node (ref "R18") (pin "1") (pinfunction "1_1") (pintype "passive"))
      (node (ref "R19") (pin "1") (pinfunction "1_1") (pintype "passive"))
      (node (ref "U1") (pin "24") (pinfunction "PC4-ADC14_24") (pintype "bidirectional"))
    )
    (net (code "45") (name "Net-(U1-PC5-ADC15)") (class "Default")
      (node (ref "R20") (pin "2") (pinfunction "2_2") (pintype "passive"))
      (node (ref "R21") (pin "2") (pinfunction "2_2") (pintype "passive"))
      (node (ref "U1") (pin "25") (pinfunction "PC5-ADC15_25") (pintype "bidirectional"))
    )
    (net (code "46") (name "Net-(U1-PH0-OSC_IN)") (class "Default")
      (node (ref "C3") (pin "1") (pinfunction "1_1") (pintype "passive"))
      (node (ref "U1") (pin "5") (pinfunction "PH0-OSC_IN_5") (pintype "input"))
      (node (ref "Y1") (pin "1") (pinfunction "1_1") (pintype "passive"))
    )
    (net (code "47") (name "Net-(U1-PH1-OSC_OUT)") (class "Default")
      (node (ref "C4") (pin "1") (pinfunction "1_1") (pintype "passive"))
      (node (ref "U1") (pin "6") (pinfunction "PH1-OSC_OUT_6") (pintype "output"))
      (node (ref "Y1") (pin "3") (pinfunction "2_3") (pintype "passive"))
    )
    (net (code "48") (name "Net-(U1-VCAP1{slash}[VSS])") (class "Default")
      (node (ref "C2") (pin "2") (pinfunction "2_2") (pintype "passive"))
      (node (ref "U1") (pin "31") (pinfunction "VCAP1/[VSS]_31") (pintype "power_in"))
    )
    (net (code "49") (name "Net-(U1-VCAP2{slash}[VSS])") (class "Default")
      (node (ref "C1") (pin "1") (pinfunction "1_1") (pintype "passive"))
      (node (ref "U1") (pin "47") (pinfunction "VCAP2/[VSS]_47") (pintype "power_in"))
    )
    (net (code "50") (name "Net-(U5-OUT)") (class "Default")
      (node (ref "SJ1") (pin "1") (pinfunction "1_1") (pintype "passive"))
      (node (ref "U5") (pin "5") (pinfunction "OUT_5") (pintype "bidirectional"))
    )
    (net (code "51") (name "Net-(U6A--IN)") (class "Default")
      (node (ref "R1") (pin "2") (pinfunction "2_2") (pintype "passive"))
      (node (ref "R3") (pin "1") (pinfunction "1_1") (pintype "passive"))
      (node (ref "U6") (pin "2") (pinfunction "-IN_2") (pintype "input"))
    )
    (net (code "52") (name "Net-(U6B--IN)") (class "Default")
      (node (ref "R2") (pin "1") (pinfunction "1_1") (pintype "passive"))
      (node (ref "R4") (pin "2") (pinfunction "2_2") (pintype "passive"))
      (node (ref "U6") (pin "6") (pinfunction "-IN_6") (pintype "input"))
    )
    (net (code "53") (name "unconnected-(J1-Pad1)") (class "Default")
      (node (ref "J1") (pin "1") (pinfunction "1_1") (pintype "passive"))
    )
    (net (code "54") (name "unconnected-(J1-Pad2)") (class "Default")
      (node (ref "J1") (pin "2") (pinfunction "2_2") (pintype "passive"))
    )
    (net (code "55") (name "unconnected-(J1-Pad3)") (class "Default")
      (node (ref "J1") (pin "3") (pinfunction "3_3") (pintype "passive"))
    )
    (net (code "56") (name "unconnected-(J1-Pad4)") (class "Default")
      (node (ref "J1") (pin "4") (pinfunction "4_4") (pintype "passive"))
    )
    (net (code "57") (name "unconnected-(U1-PA6-SPI1MISO{slash}ADC6{slash}TIM3CH1-TIM1BKIN-Pad22)") (class "Default")
      (node (ref "U1") (pin "22") (pinfunction "PA6-SPI1MISO/ADC6/TIM3CH1-TIM1BKIN_22") (pintype "bidirectional"))
    )
    (net (code "58") (name "unconnected-(U1-PA7-SPI1MOSI{slash}ADC7{slash}TIM3CH2-TIM1CH1N-Pad23)") (class "Default")
      (node (ref "U1") (pin "23") (pinfunction "PA7-SPI1MOSI/ADC7/TIM3CH2-TIM1CH1N_23") (pintype "bidirectional"))
    )
    (net (code "59") (name "unconnected-(U1-PA8-USART1CK{slash}TIM1CH1{slash}OTG_FS_SOF-Pad41)") (class "Default")
      (node (ref "U1") (pin "41") (pinfunction "PA8-USART1CK/TIM1CH1/OTG_FS_SOF_41") (pintype "bidirectional"))
    )
    (net (code "60") (name "unconnected-(U1-PA9-USART1TX{slash}TIM1CH2{slash}OTG_FS_VBUS-Pad42)") (class "Default")
      (node (ref "U1") (pin "42") (pinfunction "PA9-USART1TX/TIM1CH2/OTG_FS_VBUS_42") (pintype "bidirectional"))
    )
    (net (code "61") (name "unconnected-(U1-PA10-USART1RX{slash}TIM1CH3{slash}OTG_FS_ID-Pad43)") (class "Default")
      (node (ref "U1") (pin "43") (pinfunction "PA10-USART1RX/TIM1CH3/OTG_FS_ID_43") (pintype "bidirectional"))
    )
    (net (code "62") (name "unconnected-(U1-PA13{slash}JTMS{slash}SWDIO-Pad46)") (class "Default")
      (node (ref "U1") (pin "46") (pinfunction "PA13/JTMS/SWDIO_46") (pintype "bidirectional"))
    )
    (net (code "63") (name "unconnected-(U1-PA14{slash}JTCK{slash}SWCLK-Pad49)") (class "Default")
      (node (ref "U1") (pin "49") (pinfunction "PA14/JTCK/SWCLK_49") (pintype "bidirectional"))
    )
    (net (code "64") (name "unconnected-(U1-PA15{slash}JTDI-TIM2CH1ETR{slash}SPI1NSS-Pad50)") (class "Default")
      (node (ref "U1") (pin "50") (pinfunction "PA15/JTDI-TIM2CH1ETR/SPI1NSS_50") (pintype "bidirectional"))
    )
    (net (code "65") (name "unconnected-(U1-PB0-ADC8{slash}TIM3CH3-TIM1CH2N{slash}OTG_HS_ULPI_D1-Pad26)") (class "Default")
      (node (ref "U1") (pin "26") (pinfunction "PB0-ADC8/TIM3CH3-TIM1CH2N/OTG_HS_ULPI_D1_26") (pintype "bidirectional"))
    )
    (net (code "66") (name "unconnected-(U1-PB1-ADC9{slash}TIM3CH4-TIM1CH3N{slash}OTG_HS_ULPI_D2-Pad27)") (class "Default")
      (node (ref "U1") (pin "27") (pinfunction "PB1-ADC9/TIM3CH4-TIM1CH3N/OTG_HS_ULPI_D2_27") (pintype "bidirectional"))
    )
    (net (code "67") (name "unconnected-(U1-PB4{slash}JNTRST-TIM3CH1{slash}SPI1MISO-Pad56)") (class "Default")
      (node (ref "U1") (pin "56") (pinfunction "PB4/JNTRST-TIM3CH1/SPI1MISO_56") (pintype "bidirectional"))
    )
    (net (code "68") (name "unconnected-(U1-PB5-I2C1SMBAI-TIM3CH2{slash}CAN2_RX-Pad57)") (class "Default")
      (node (ref "U1") (pin "57") (pinfunction "PB5-I2C1SMBAI-TIM3CH2/CAN2_RX_57") (pintype "bidirectional"))
    )
    (net (code "69") (name "unconnected-(U1-PB6-I2C1SCL{slash}TIM4CH1-USART1TX{slash}CAN2_TX-Pad58)") (class "Default")
      (node (ref "U1") (pin "58") (pinfunction "PB6-I2C1SCL/TIM4CH1-USART1TX/CAN2_TX_58") (pintype "bidirectional"))
    )
    (net (code "70") (name "unconnected-(U1-PB7-I2C1SDA{slash}TIM4CH2-USART1RX-Pad59)") (class "Default")
      (node (ref "U1") (pin "59") (pinfunction "PB7-I2C1SDA/TIM4CH2-USART1RX_59") (pintype "bidirectional"))
    )
    (net (code "71") (name "unconnected-(U1-PB10-I2C2SCL{slash}TIM2CH3{slash}OTG_HS_ULPI_D3-Pad29)") (class "Default")
      (node (ref "U1") (pin "29") (pinfunction "PB10-I2C2SCL/TIM2CH3/OTG_HS_ULPI_D3_29") (pintype "bidirectional"))
    )
    (net (code "72") (name "unconnected-(U1-PB12-SPI2NSS{slash}I2C2SMBAI{slash}CAN2_RX-Pad33)") (class "Default")
      (node (ref "U1") (pin "33") (pinfunction "PB12-SPI2NSS/I2C2SMBAI/CAN2_RX_33") (pintype "bidirectional"))
    )
    (net (code "73") (name "unconnected-(U1-PB13-SPI2SCK{slash}CAN2_TX-Pad34)") (class "Default")
      (node (ref "U1") (pin "34") (pinfunction "PB13-SPI2SCK/CAN2_TX_34") (pintype "bidirectional"))
    )
    (net (code "74") (name "unconnected-(U1-PB14-SPI2MISO{slash}TIM1CH2N{slash}OTG_HS_DM-Pad35)") (class "Default")
      (node (ref "U1") (pin "35") (pinfunction "PB14-SPI2MISO/TIM1CH2N/OTG_HS_DM_35") (pintype "bidirectional"))
    )
    (net (code "75") (name "unconnected-(U1-PB15-SPI2MOSI{slash}TIM1CH3N{slash}OTG_HS_DP-Pad36)") (class "Default")
      (node (ref "U1") (pin "36") (pinfunction "PB15-SPI2MOSI/TIM1CH3N/OTG_HS_DP_36") (pintype "bidirectional"))
    )
    (net (code "76") (name "unconnected-(U1-PC6-TIM3CH1-Pad37)") (class "Default")
      (node (ref "U1") (pin "37") (pinfunction "PC6-TIM3CH1_37") (pintype "bidirectional"))
    )
    (net (code "77") (name "unconnected-(U1-PC7-TIM3CH2-Pad38)") (class "Default")
      (node (ref "U1") (pin "38") (pinfunction "PC7-TIM3CH2_38") (pintype "bidirectional"))
    )
    (net (code "78") (name "unconnected-(U1-PC8-TIM3CH3-Pad39)") (class "Default")
      (node (ref "U1") (pin "39") (pinfunction "PC8-TIM3CH3_39") (pintype "bidirectional"))
    )
    (net (code "79") (name "unconnected-(U1-PC9-TIM3CH4-Pad40)") (class "Default")
      (node (ref "U1") (pin "40") (pinfunction "PC9-TIM3CH4_40") (pintype "bidirectional"))
    )
    (net (code "80") (name "unconnected-(U1-PC10-USART3TX-Pad51)") (class "Default")
      (node (ref "U1") (pin "51") (pinfunction "PC10-USART3TX_51") (pintype "bidirectional"))
    )
    (net (code "81") (name "unconnected-(U1-PC11-USART3RX-Pad52)") (class "Default")
      (node (ref "U1") (pin "52") (pinfunction "PC11-USART3RX_52") (pintype "bidirectional"))
    )
    (net (code "82") (name "unconnected-(U1-PC12-USART3CK{slash}UART5_TX-Pad53)") (class "Default")
      (node (ref "U1") (pin "53") (pinfunction "PC12-USART3CK/UART5_TX_53") (pintype "bidirectional"))
    )
    (net (code "83") (name "unconnected-(U1-PC13-RTC_AF1-Pad2)") (class "Default")
      (node (ref "U1") (pin "2") (pinfunction "PC13-RTC_AF1_2") (pintype "bidirectional"))
    )
    (net (code "84") (name "unconnected-(U1-PC14-OSC32_IN-Pad3)") (class "Default")
      (node (ref "U1") (pin "3") (pinfunction "PC14-OSC32_IN_3") (pintype "bidirectional"))
    )
    (net (code "85") (name "unconnected-(U1-PC15-OSC32_OUT-Pad4)") (class "Default")
      (node (ref "U1") (pin "4") (pinfunction "PC15-OSC32_OUT_4") (pintype "bidirectional"))
    )
    (net (code "86") (name "unconnected-(U1-PD2-TIM3ETR{slash}UART5_RX-Pad54)") (class "Default")
      (node (ref "U1") (pin "54") (pinfunction "PD2-TIM3ETR/UART5_RX_54") (pintype "bidirectional"))
    )
    (net (code "87") (name "unconnected-(U2-NC-Pad4)") (class "Default")
      (node (ref "U2") (pin "4") (pinfunction "NC_4") (pintype "no_connect"))
    )
    (net (code "88") (name "unconnected-(U3-NC_OR_ADJ-Pad4)") (class "Default")
      (node (ref "U3") (pin "4") (pinfunction "NC_OR_ADJ_4") (pintype "bidirectional"))
    )
    (net (code "89") (name "unconnected-(U5-NC-Pad4)") (class "Default")
      (node (ref "U5") (pin "4") (pinfunction "NC_4") (pintype "no_connect"))
    )
  )
)
